# Pure_Sequencer.net
KiCad netlist of a schematic drawn in EAGLE
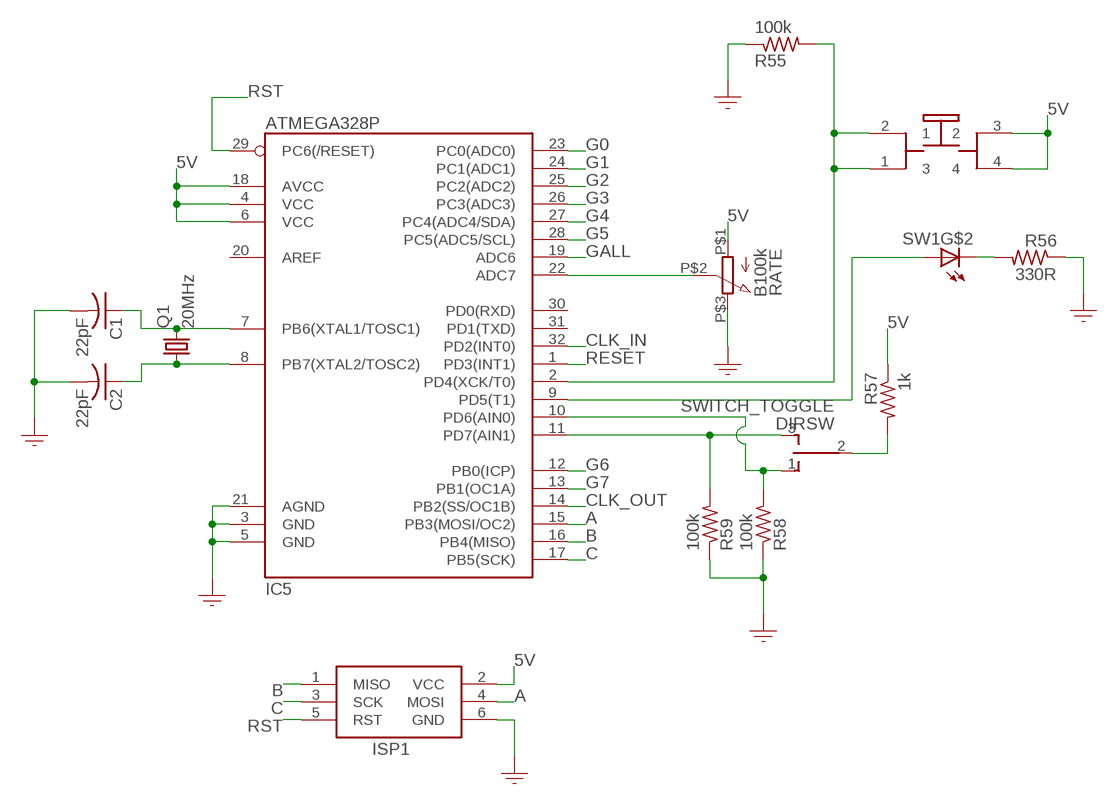
[diagram p0: schematic, sheet 1]
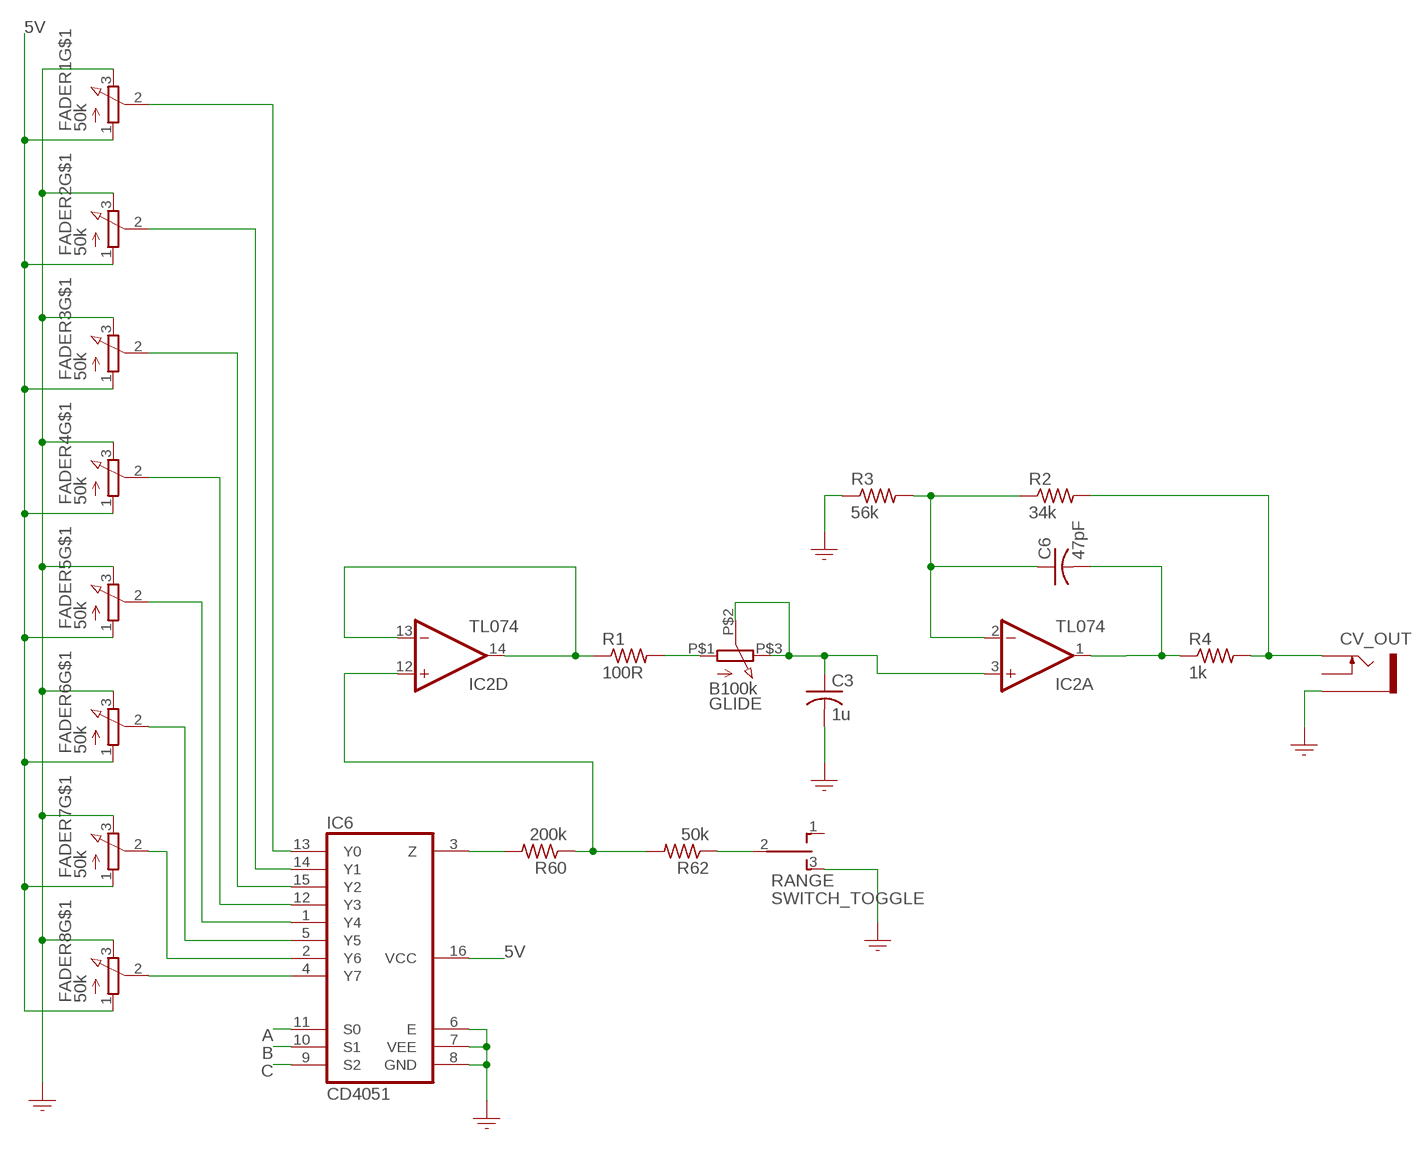
[diagram p1: schematic, sheet 2]
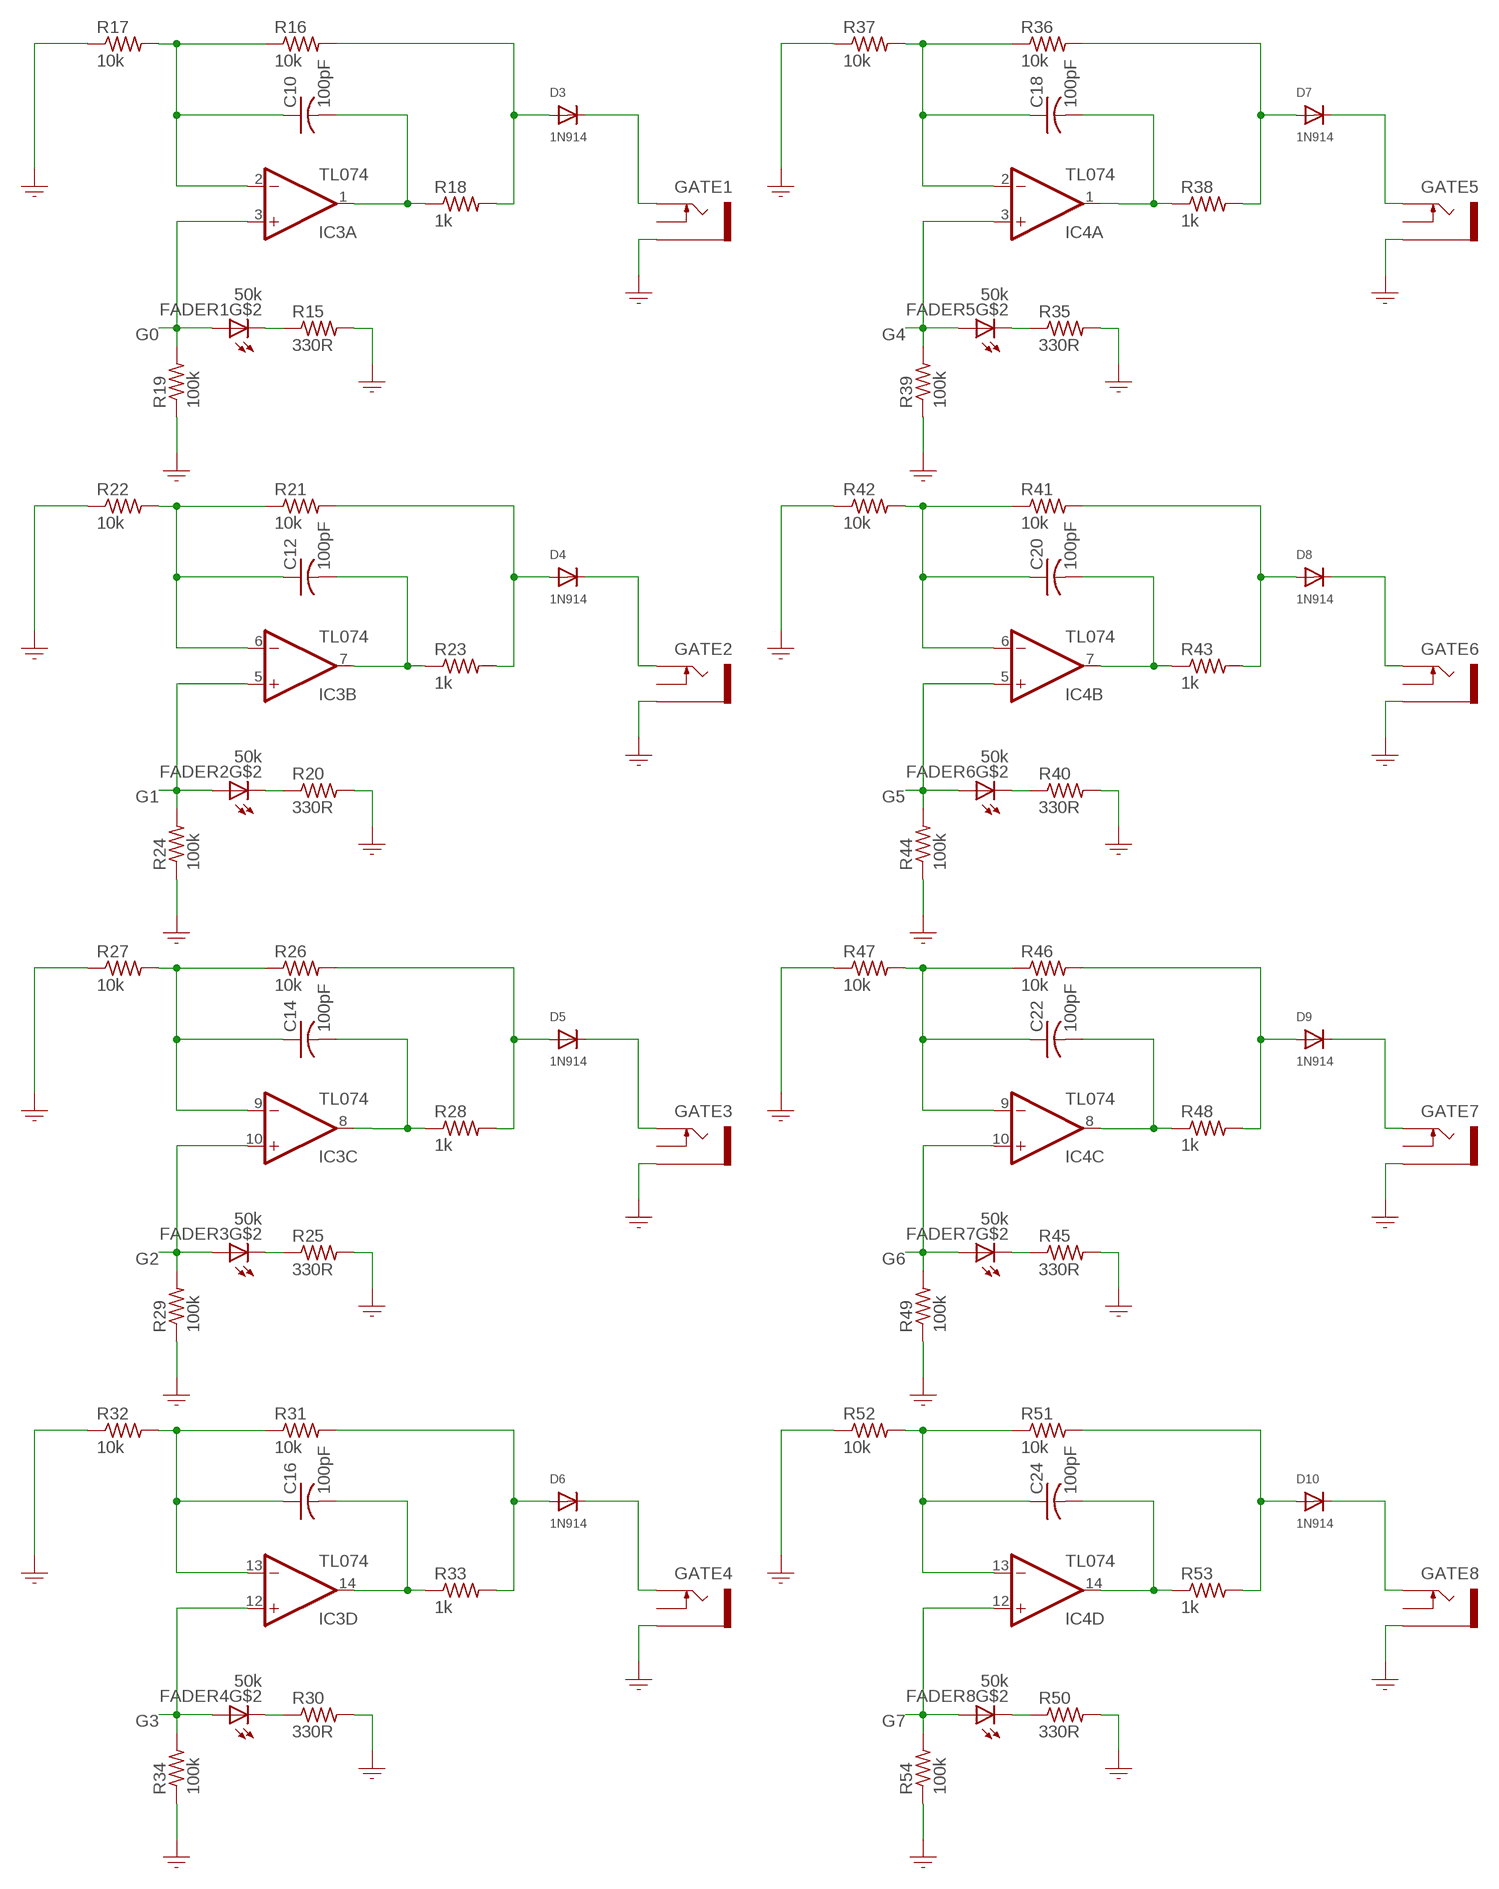
[diagram p2: schematic, sheet 3]
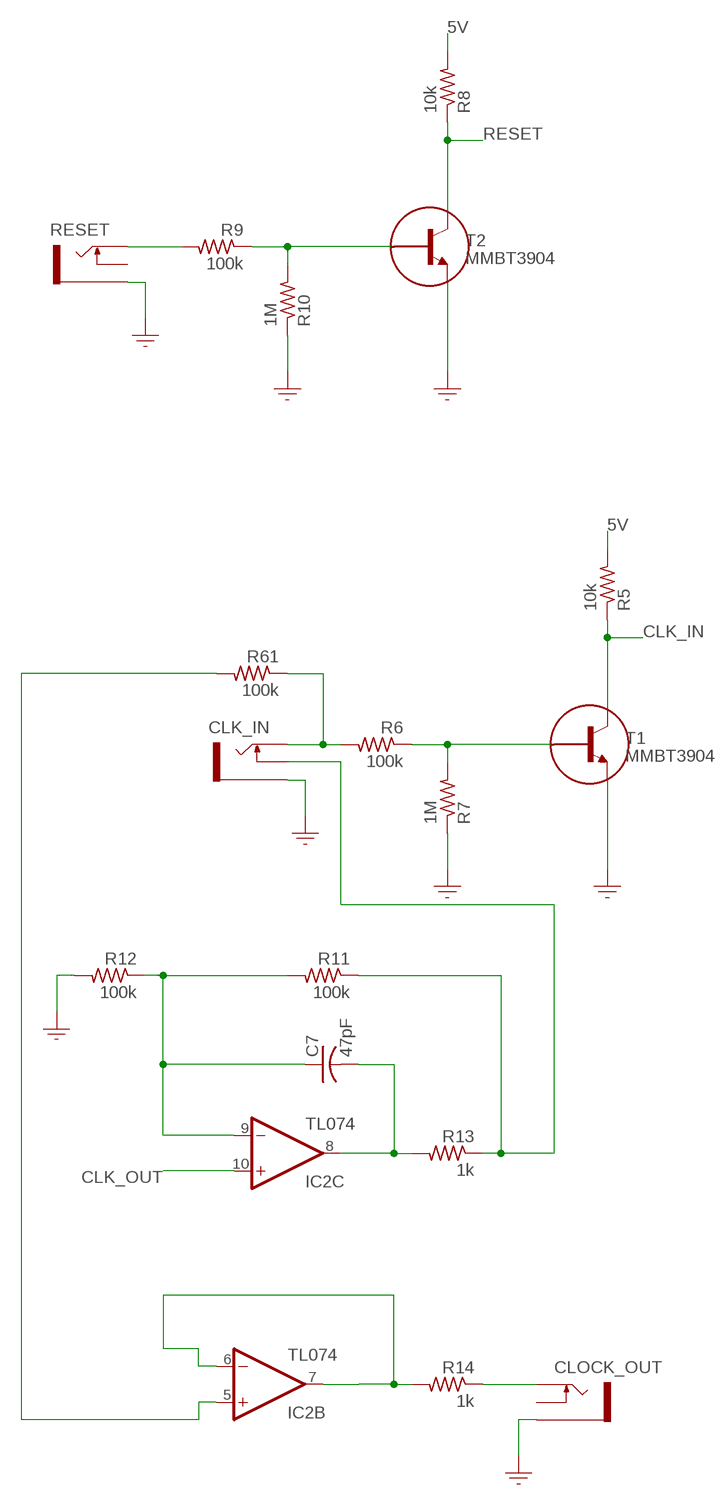
[diagram p3: schematic, sheet 4]
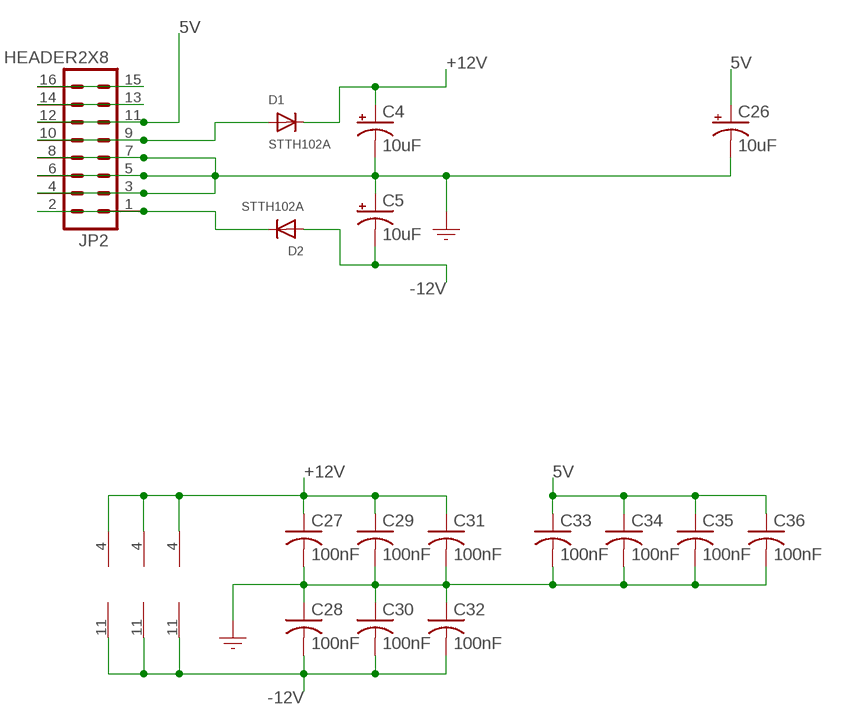
[diagram p4: schematic, sheet 5]

(export (version "E")
  (design (tool "Eeschema 10.0.6"))
  (components
    (comp (ref "C7")
      (value "47pF")
      (footprint "eagle-import:C0805")
      (libsource (lib "eagle-import") (part "CAPACITOR-USC0805"))
    )
    (comp (ref "CLK_IN")
      (value "PJ301M-12")
      (footprint "eagle-import:PJ301M-12")
      (libsource (lib "eagle-import") (part "SOCKET_MONO_3.5MMPJ301M-12"))
    )
    (comp (ref "CLOCK_OUT")
      (value "PJ301M-12")
      (footprint "eagle-import:PJ301M-12")
      (libsource (lib "eagle-import") (part "SOCKET_MONO_3.5MMPJ301M-12"))
    )
    (comp (ref "IC2")
      (value "TL074")
      (footprint "eagle-import:SO14")
      (libsource (lib "eagle-import") (part "OPAMP_QUADD"))
    )
    (comp (ref "R5")
      (value "10k")
      (footprint "eagle-import:R0805")
      (libsource (lib "eagle-import") (part "RESISTOR_USR0805"))
    )
    (comp (ref "R6")
      (value "100k")
      (footprint "eagle-import:R0805")
      (libsource (lib "eagle-import") (part "RESISTOR_USR0805"))
    )
    (comp (ref "R7")
      (value "1M")
      (footprint "eagle-import:R0805")
      (libsource (lib "eagle-import") (part "RESISTOR_USR0805"))
    )
    (comp (ref "R8")
      (value "10k")
      (footprint "eagle-import:R0805")
      (libsource (lib "eagle-import") (part "RESISTOR_USR0805"))
    )
    (comp (ref "R9")
      (value "100k")
      (footprint "eagle-import:R0805")
      (libsource (lib "eagle-import") (part "RESISTOR_USR0805"))
    )
    (comp (ref "R10")
      (value "1M")
      (footprint "eagle-import:R0805")
      (libsource (lib "eagle-import") (part "RESISTOR_USR0805"))
    )
    (comp (ref "R11")
      (value "100k")
      (footprint "eagle-import:R0805")
      (libsource (lib "eagle-import") (part "RESISTOR_USR0805"))
    )
    (comp (ref "R12")
      (value "100k")
      (footprint "eagle-import:R0805")
      (libsource (lib "eagle-import") (part "RESISTOR_USR0805"))
    )
    (comp (ref "R13")
      (value "1k")
      (footprint "eagle-import:R0805")
      (libsource (lib "eagle-import") (part "RESISTOR_USR0805"))
    )
    (comp (ref "R14")
      (value "1k")
      (footprint "eagle-import:R0805")
      (libsource (lib "eagle-import") (part "RESISTOR_USR0805"))
    )
    (comp (ref "R61")
      (value "100k")
      (footprint "eagle-import:R0805")
      (libsource (lib "eagle-import") (part "RESISTOR_USR0805"))
    )
    (comp (ref "RESET")
      (value "PJ301M-12")
      (footprint "eagle-import:PJ301M-12")
      (libsource (lib "eagle-import") (part "SOCKET_MONO_3.5MMPJ301M-12"))
    )
    (comp (ref "T1")
      (value "MMBT3904")
      (footprint "eagle-import:SOT23")
      (libsource (lib "eagle-import") (part "TRANSISTOR_NPNSOT23"))
    )
    (comp (ref "T2")
      (value "MMBT3904")
      (footprint "eagle-import:SOT23")
      (libsource (lib "eagle-import") (part "TRANSISTOR_NPNSOT23"))
    )
    (comp (ref "C3")
      (value "1u")
      (footprint "eagle-import:C0805")
      (libsource (lib "eagle-import") (part "CAPACITOR-USC0805"))
    )
    (comp (ref "C6")
      (value "47pF")
      (footprint "eagle-import:C0805")
      (libsource (lib "eagle-import") (part "CAPACITOR-USC0805"))
    )
    (comp (ref "CV_OUT")
      (value "PJ301M-12")
      (footprint "eagle-import:PJ301M-12")
      (libsource (lib "eagle-import") (part "SOCKET_MONO_3.5MMPJ301M-12"))
    )
    (comp (ref "FADER1")
      (value "50k")
      (footprint "eagle-import:FADER_20MM_LED")
      (libsource (lib "eagle-import") (part "RESISTOR_VARIABLE_LED"))
    )
    (comp (ref "FADER2")
      (value "50k")
      (footprint "eagle-import:FADER_20MM_LED")
      (libsource (lib "eagle-import") (part "RESISTOR_VARIABLE_LED"))
    )
    (comp (ref "FADER3")
      (value "50k")
      (footprint "eagle-import:FADER_20MM_LED")
      (libsource (lib "eagle-import") (part "RESISTOR_VARIABLE_LED"))
    )
    (comp (ref "FADER4")
      (value "50k")
      (footprint "eagle-import:FADER_20MM_LED")
      (libsource (lib "eagle-import") (part "RESISTOR_VARIABLE_LED"))
    )
    (comp (ref "FADER5")
      (value "50k")
      (footprint "eagle-import:FADER_20MM_LED")
      (libsource (lib "eagle-import") (part "RESISTOR_VARIABLE_LED"))
    )
    (comp (ref "FADER6")
      (value "50k")
      (footprint "eagle-import:FADER_20MM_LED")
      (libsource (lib "eagle-import") (part "RESISTOR_VARIABLE_LED"))
    )
    (comp (ref "FADER7")
      (value "50k")
      (footprint "eagle-import:FADER_20MM_LED")
      (libsource (lib "eagle-import") (part "RESISTOR_VARIABLE_LED"))
    )
    (comp (ref "FADER8")
      (value "50k")
      (footprint "eagle-import:FADER_20MM_LED")
      (libsource (lib "eagle-import") (part "RESISTOR_VARIABLE_LED"))
    )
    (comp (ref "GLIDE")
      (value "B100k")
      (footprint "eagle-import:POTENTIOMETER_9MM")
      (libsource (lib "eagle-import") (part "RESISTOR_VARIABLE9MM_POT"))
    )
    (comp (ref "IC6")
      (value "CD4051")
      (footprint "eagle-import:SOIC_16")
      (libsource (lib "eagle-import") (part "MUX_1X8_CD4051"))
    )
    (comp (ref "R1")
      (value "100R")
      (footprint "eagle-import:R0805")
      (libsource (lib "eagle-import") (part "RESISTOR_USR0805"))
    )
    (comp (ref "R2")
      (value "34k")
      (footprint "eagle-import:R0805")
      (libsource (lib "eagle-import") (part "RESISTOR_USR0805"))
    )
    (comp (ref "R3")
      (value "56k")
      (footprint "eagle-import:R0805")
      (libsource (lib "eagle-import") (part "RESISTOR_USR0805"))
    )
    (comp (ref "R4")
      (value "1k")
      (footprint "eagle-import:R0805")
      (libsource (lib "eagle-import") (part "RESISTOR_USR0805"))
    )
    (comp (ref "R60")
      (value "200k")
      (footprint "eagle-import:R0805")
      (libsource (lib "eagle-import") (part "RESISTOR_USR0805"))
    )
    (comp (ref "R62")
      (value "50k")
      (footprint "eagle-import:R0805")
      (libsource (lib "eagle-import") (part "RESISTOR_USR0805"))
    )
    (comp (ref "RANGE")
      (value "SWITCH_TOGGLE")
      (footprint "eagle-import:TOGGLE_SW")
      (libsource (lib "eagle-import") (part "SWITCH_TOGGLE"))
    )
    (comp (ref "C10")
      (value "100pF")
      (footprint "eagle-import:C0805")
      (libsource (lib "eagle-import") (part "CAPACITOR-USC0805"))
    )
    (comp (ref "C12")
      (value "100pF")
      (footprint "eagle-import:C0805")
      (libsource (lib "eagle-import") (part "CAPACITOR-USC0805"))
    )
    (comp (ref "C14")
      (value "100pF")
      (footprint "eagle-import:C0805")
      (libsource (lib "eagle-import") (part "CAPACITOR-USC0805"))
    )
    (comp (ref "C16")
      (value "100pF")
      (footprint "eagle-import:C0805")
      (libsource (lib "eagle-import") (part "CAPACITOR-USC0805"))
    )
    (comp (ref "C18")
      (value "100pF")
      (footprint "eagle-import:C0805")
      (libsource (lib "eagle-import") (part "CAPACITOR-USC0805"))
    )
    (comp (ref "C20")
      (value "100pF")
      (footprint "eagle-import:C0805")
      (libsource (lib "eagle-import") (part "CAPACITOR-USC0805"))
    )
    (comp (ref "C22")
      (value "100pF")
      (footprint "eagle-import:C0805")
      (libsource (lib "eagle-import") (part "CAPACITOR-USC0805"))
    )
    (comp (ref "C24")
      (value "100pF")
      (footprint "eagle-import:C0805")
      (libsource (lib "eagle-import") (part "CAPACITOR-USC0805"))
    )
    (comp (ref "D3")
      (value "1N914")
      (footprint "eagle-import:DO-41")
      (libsource (lib "eagle-import") (part "DIODEDO-41"))
    )
    (comp (ref "D4")
      (value "1N914")
      (footprint "eagle-import:DO-41")
      (libsource (lib "eagle-import") (part "DIODEDO-41"))
    )
    (comp (ref "D5")
      (value "1N914")
      (footprint "eagle-import:DO-41")
      (libsource (lib "eagle-import") (part "DIODEDO-41"))
    )
    (comp (ref "D6")
      (value "1N914")
      (footprint "eagle-import:DO-41")
      (libsource (lib "eagle-import") (part "DIODEDO-41"))
    )
    (comp (ref "D7")
      (value "1N914")
      (footprint "eagle-import:DO-41")
      (libsource (lib "eagle-import") (part "DIODEDO-41"))
    )
    (comp (ref "D8")
      (value "1N914")
      (footprint "eagle-import:DO-41")
      (libsource (lib "eagle-import") (part "DIODEDO-41"))
    )
    (comp (ref "D9")
      (value "1N914")
      (footprint "eagle-import:DO-41")
      (libsource (lib "eagle-import") (part "DIODEDO-41"))
    )
    (comp (ref "D10")
      (value "1N914")
      (footprint "eagle-import:DO-41")
      (libsource (lib "eagle-import") (part "DIODEDO-41"))
    )
    (comp (ref "GATE1")
      (value "PJ301M-12")
      (footprint "eagle-import:PJ301M-12")
      (libsource (lib "eagle-import") (part "SOCKET_MONO_3.5MMPJ301M-12"))
    )
    (comp (ref "GATE2")
      (value "PJ301M-12")
      (footprint "eagle-import:PJ301M-12")
      (libsource (lib "eagle-import") (part "SOCKET_MONO_3.5MMPJ301M-12"))
    )
    (comp (ref "GATE3")
      (value "PJ301M-12")
      (footprint "eagle-import:PJ301M-12")
      (libsource (lib "eagle-import") (part "SOCKET_MONO_3.5MMPJ301M-12"))
    )
    (comp (ref "GATE4")
      (value "PJ301M-12")
      (footprint "eagle-import:PJ301M-12")
      (libsource (lib "eagle-import") (part "SOCKET_MONO_3.5MMPJ301M-12"))
    )
    (comp (ref "GATE5")
      (value "PJ301M-12")
      (footprint "eagle-import:PJ301M-12")
      (libsource (lib "eagle-import") (part "SOCKET_MONO_3.5MMPJ301M-12"))
    )
    (comp (ref "GATE6")
      (value "PJ301M-12")
      (footprint "eagle-import:PJ301M-12")
      (libsource (lib "eagle-import") (part "SOCKET_MONO_3.5MMPJ301M-12"))
    )
    (comp (ref "GATE7")
      (value "PJ301M-12")
      (footprint "eagle-import:PJ301M-12")
      (libsource (lib "eagle-import") (part "SOCKET_MONO_3.5MMPJ301M-12"))
    )
    (comp (ref "GATE8")
      (value "PJ301M-12")
      (footprint "eagle-import:PJ301M-12")
      (libsource (lib "eagle-import") (part "SOCKET_MONO_3.5MMPJ301M-12"))
    )
    (comp (ref "IC3")
      (value "TL074")
      (footprint "eagle-import:SO14")
      (libsource (lib "eagle-import") (part "OPAMP_QUADD"))
    )
    (comp (ref "IC4")
      (value "TL074")
      (footprint "eagle-import:SO14")
      (libsource (lib "eagle-import") (part "OPAMP_QUADD"))
    )
    (comp (ref "R15")
      (value "330R")
      (footprint "eagle-import:R0805")
      (libsource (lib "eagle-import") (part "RESISTOR_USR0805"))
    )
    (comp (ref "R16")
      (value "10k")
      (footprint "eagle-import:R0805")
      (libsource (lib "eagle-import") (part "RESISTOR_USR0805"))
    )
    (comp (ref "R17")
      (value "10k")
      (footprint "eagle-import:R0805")
      (libsource (lib "eagle-import") (part "RESISTOR_USR0805"))
    )
    (comp (ref "R18")
      (value "1k")
      (footprint "eagle-import:R0805")
      (libsource (lib "eagle-import") (part "RESISTOR_USR0805"))
    )
    (comp (ref "R19")
      (value "100k")
      (footprint "eagle-import:R0805")
      (libsource (lib "eagle-import") (part "RESISTOR_USR0805"))
    )
    (comp (ref "R20")
      (value "330R")
      (footprint "eagle-import:R0805")
      (libsource (lib "eagle-import") (part "RESISTOR_USR0805"))
    )
    (comp (ref "R21")
      (value "10k")
      (footprint "eagle-import:R0805")
      (libsource (lib "eagle-import") (part "RESISTOR_USR0805"))
    )
    (comp (ref "R22")
      (value "10k")
      (footprint "eagle-import:R0805")
      (libsource (lib "eagle-import") (part "RESISTOR_USR0805"))
    )
    (comp (ref "R23")
      (value "1k")
      (footprint "eagle-import:R0805")
      (libsource (lib "eagle-import") (part "RESISTOR_USR0805"))
    )
    (comp (ref "R24")
      (value "100k")
      (footprint "eagle-import:R0805")
      (libsource (lib "eagle-import") (part "RESISTOR_USR0805"))
    )
    (comp (ref "R25")
      (value "330R")
      (footprint "eagle-import:R0805")
      (libsource (lib "eagle-import") (part "RESISTOR_USR0805"))
    )
    (comp (ref "R26")
      (value "10k")
      (footprint "eagle-import:R0805")
      (libsource (lib "eagle-import") (part "RESISTOR_USR0805"))
    )
    (comp (ref "R27")
      (value "10k")
      (footprint "eagle-import:R0805")
      (libsource (lib "eagle-import") (part "RESISTOR_USR0805"))
    )
    (comp (ref "R28")
      (value "1k")
      (footprint "eagle-import:R0805")
      (libsource (lib "eagle-import") (part "RESISTOR_USR0805"))
    )
    (comp (ref "R29")
      (value "100k")
      (footprint "eagle-import:R0805")
      (libsource (lib "eagle-import") (part "RESISTOR_USR0805"))
    )
    (comp (ref "R30")
      (value "330R")
      (footprint "eagle-import:R0805")
      (libsource (lib "eagle-import") (part "RESISTOR_USR0805"))
    )
    (comp (ref "R31")
      (value "10k")
      (footprint "eagle-import:R0805")
      (libsource (lib "eagle-import") (part "RESISTOR_USR0805"))
    )
    (comp (ref "R32")
      (value "10k")
      (footprint "eagle-import:R0805")
      (libsource (lib "eagle-import") (part "RESISTOR_USR0805"))
    )
    (comp (ref "R33")
      (value "1k")
      (footprint "eagle-import:R0805")
      (libsource (lib "eagle-import") (part "RESISTOR_USR0805"))
    )
    (comp (ref "R34")
      (value "100k")
      (footprint "eagle-import:R0805")
      (libsource (lib "eagle-import") (part "RESISTOR_USR0805"))
    )
    (comp (ref "R35")
      (value "330R")
      (footprint "eagle-import:R0805")
      (libsource (lib "eagle-import") (part "RESISTOR_USR0805"))
    )
    (comp (ref "R36")
      (value "10k")
      (footprint "eagle-import:R0805")
      (libsource (lib "eagle-import") (part "RESISTOR_USR0805"))
    )
    (comp (ref "R37")
      (value "10k")
      (footprint "eagle-import:R0805")
      (libsource (lib "eagle-import") (part "RESISTOR_USR0805"))
    )
    (comp (ref "R38")
      (value "1k")
      (footprint "eagle-import:R0805")
      (libsource (lib "eagle-import") (part "RESISTOR_USR0805"))
    )
    (comp (ref "R39")
      (value "100k")
      (footprint "eagle-import:R0805")
      (libsource (lib "eagle-import") (part "RESISTOR_USR0805"))
    )
    (comp (ref "R40")
      (value "330R")
      (footprint "eagle-import:R0805")
      (libsource (lib "eagle-import") (part "RESISTOR_USR0805"))
    )
    (comp (ref "R41")
      (value "10k")
      (footprint "eagle-import:R0805")
      (libsource (lib "eagle-import") (part "RESISTOR_USR0805"))
    )
    (comp (ref "R42")
      (value "10k")
      (footprint "eagle-import:R0805")
      (libsource (lib "eagle-import") (part "RESISTOR_USR0805"))
    )
    (comp (ref "R43")
      (value "1k")
      (footprint "eagle-import:R0805")
      (libsource (lib "eagle-import") (part "RESISTOR_USR0805"))
    )
    (comp (ref "R44")
      (value "100k")
      (footprint "eagle-import:R0805")
      (libsource (lib "eagle-import") (part "RESISTOR_USR0805"))
    )
    (comp (ref "R45")
      (value "330R")
      (footprint "eagle-import:R0805")
      (libsource (lib "eagle-import") (part "RESISTOR_USR0805"))
    )
    (comp (ref "R46")
      (value "10k")
      (footprint "eagle-import:R0805")
      (libsource (lib "eagle-import") (part "RESISTOR_USR0805"))
    )
    (comp (ref "R47")
      (value "10k")
      (footprint "eagle-import:R0805")
      (libsource (lib "eagle-import") (part "RESISTOR_USR0805"))
    )
    (comp (ref "R48")
      (value "1k")
      (footprint "eagle-import:R0805")
      (libsource (lib "eagle-import") (part "RESISTOR_USR0805"))
    )
    (comp (ref "R49")
      (value "100k")
      (footprint "eagle-import:R0805")
      (libsource (lib "eagle-import") (part "RESISTOR_USR0805"))
    )
    (comp (ref "R50")
      (value "330R")
      (footprint "eagle-import:R0805")
      (libsource (lib "eagle-import") (part "RESISTOR_USR0805"))
    )
    (comp (ref "R51")
      (value "10k")
      (footprint "eagle-import:R0805")
      (libsource (lib "eagle-import") (part "RESISTOR_USR0805"))
    )
    (comp (ref "R52")
      (value "10k")
      (footprint "eagle-import:R0805")
      (libsource (lib "eagle-import") (part "RESISTOR_USR0805"))
    )
    (comp (ref "R53")
      (value "1k")
      (footprint "eagle-import:R0805")
      (libsource (lib "eagle-import") (part "RESISTOR_USR0805"))
    )
    (comp (ref "R54")
      (value "100k")
      (footprint "eagle-import:R0805")
      (libsource (lib "eagle-import") (part "RESISTOR_USR0805"))
    )
    (comp (ref "C1")
      (value "22pF")
      (footprint "eagle-import:C0805")
      (libsource (lib "eagle-import") (part "CAPACITOR-USC0805"))
    )
    (comp (ref "C2")
      (value "22pF")
      (footprint "eagle-import:C0805")
      (libsource (lib "eagle-import") (part "CAPACITOR-USC0805"))
    )
    (comp (ref "DIRSW")
      (value "SWITCH_TOGGLE")
      (footprint "eagle-import:TOGGLE_SW")
      (libsource (lib "eagle-import") (part "SWITCH_TOGGLE"))
    )
    (comp (ref "IC5")
      (value "ATMEGA328P")
      (footprint "eagle-import:TQFP32-08")
      (libsource (lib "eagle-import") (part "MICROPROCESSOR_ATMEGA328_SMT"))
    )
    (comp (ref "ISP1")
      (value "HEADER2X3-6")
      (footprint "eagle-import:AVRISP")
      (libsource (lib "eagle-import") (part "HEADER2X3-6"))
    )
    (comp (ref "Q1")
      (value "20MHz")
      (footprint "eagle-import:HC49UP")
      (libsource (lib "eagle-import") (part "CRYSTALHC49UP"))
    )
    (comp (ref "R55")
      (value "100k")
      (footprint "eagle-import:R0805")
      (libsource (lib "eagle-import") (part "RESISTOR_USR0805"))
    )
    (comp (ref "R56")
      (value "330R")
      (footprint "eagle-import:R0805")
      (libsource (lib "eagle-import") (part "RESISTOR_USR0805"))
    )
    (comp (ref "R57")
      (value "1k")
      (footprint "eagle-import:R0805")
      (libsource (lib "eagle-import") (part "RESISTOR_USR0805"))
    )
    (comp (ref "R58")
      (value "100k")
      (footprint "eagle-import:R0805")
      (libsource (lib "eagle-import") (part "RESISTOR_USR0805"))
    )
    (comp (ref "R59")
      (value "100k")
      (footprint "eagle-import:R0805")
      (libsource (lib "eagle-import") (part "RESISTOR_USR0805"))
    )
    (comp (ref "RATE")
      (value "B100k")
      (footprint "eagle-import:POTENTIOMETER_9MM")
      (libsource (lib "eagle-import") (part "RESISTOR_VARIABLE9MM_POT"))
    )
    (comp (ref "SW1")
      (value "SWITCH_PUSHBUTTON_LED")
      (footprint "eagle-import:PB6149L")
      (libsource (lib "eagle-import") (part "SWITCH_PUSHBUTTON_LED"))
    )
    (comp (ref "C4")
      (value "10uF")
      (footprint "eagle-import:153CLV-0505")
      (libsource (lib "eagle-import") (part "CAPACITOR_POL-US153CLV-0505"))
    )
    (comp (ref "C5")
      (value "10uF")
      (footprint "eagle-import:153CLV-0505")
      (libsource (lib "eagle-import") (part "CAPACITOR_POL-US153CLV-0505"))
    )
    (comp (ref "C26")
      (value "10uF")
      (footprint "eagle-import:153CLV-0505")
      (libsource (lib "eagle-import") (part "CAPACITOR_POL-US153CLV-0505"))
    )
    (comp (ref "C27")
      (value "100nF")
      (footprint "eagle-import:C0805")
      (libsource (lib "eagle-import") (part "CAPACITOR-USC0805"))
    )
    (comp (ref "C28")
      (value "100nF")
      (footprint "eagle-import:C0805")
      (libsource (lib "eagle-import") (part "CAPACITOR-USC0805"))
    )
    (comp (ref "C29")
      (value "100nF")
      (footprint "eagle-import:C0805")
      (libsource (lib "eagle-import") (part "CAPACITOR-USC0805"))
    )
    (comp (ref "C30")
      (value "100nF")
      (footprint "eagle-import:C0805")
      (libsource (lib "eagle-import") (part "CAPACITOR-USC0805"))
    )
    (comp (ref "C31")
      (value "100nF")
      (footprint "eagle-import:C0805")
      (libsource (lib "eagle-import") (part "CAPACITOR-USC0805"))
    )
    (comp (ref "C32")
      (value "100nF")
      (footprint "eagle-import:C0805")
      (libsource (lib "eagle-import") (part "CAPACITOR-USC0805"))
    )
    (comp (ref "C33")
      (value "100nF")
      (footprint "eagle-import:C0805")
      (libsource (lib "eagle-import") (part "CAPACITOR-USC0805"))
    )
    (comp (ref "C34")
      (value "100nF")
      (footprint "eagle-import:C0805")
      (libsource (lib "eagle-import") (part "CAPACITOR-USC0805"))
    )
    (comp (ref "C35")
      (value "100nF")
      (footprint "eagle-import:C0805")
      (libsource (lib "eagle-import") (part "CAPACITOR-USC0805"))
    )
    (comp (ref "C36")
      (value "100nF")
      (footprint "eagle-import:C0805")
      (libsource (lib "eagle-import") (part "CAPACITOR-USC0805"))
    )
    (comp (ref "D1")
      (value "STTH102A")
      (footprint "eagle-import:SMADIODE")
      (libsource (lib "eagle-import") (part "DIODESMA"))
    )
    (comp (ref "D2")
      (value "STTH102A")
      (footprint "eagle-import:SMADIODE")
      (libsource (lib "eagle-import") (part "DIODESMA"))
    )
    (comp (ref "JP2")
      (value "HEADER2X8")
      (footprint "eagle-import:POWER_SHROUDED")
      (libsource (lib "eagle-import") (part "HEADER2X8"))
    )
  )
  (nets
    (net (code "1") (name "+12V") (class "Default")
      (node (ref "C27") (pin "1") (pinfunction "1_1") (pintype "passive"))
      (node (ref "C29") (pin "1") (pinfunction "1_1") (pintype "passive"))
      (node (ref "C31") (pin "1") (pinfunction "1_1") (pintype "passive"))
      (node (ref "C4") (pin "+") (pinfunction "+_+") (pintype "passive"))
      (node (ref "D1") (pin "C") (pinfunction "C_C") (pintype "passive"))
      (node (ref "IC2") (pin "4") (pinfunction "V+_4") (pintype "power_in"))
      (node (ref "IC3") (pin "4") (pinfunction "V+_4") (pintype "power_in"))
      (node (ref "IC4") (pin "4") (pinfunction "V+_4") (pintype "power_in"))
    )
    (net (code "2") (name "-12V") (class "Default")
      (node (ref "C28") (pin "2") (pinfunction "2_2") (pintype "passive"))
      (node (ref "C30") (pin "2") (pinfunction "2_2") (pintype "passive"))
      (node (ref "C32") (pin "2") (pinfunction "2_2") (pintype "passive"))
      (node (ref "C5") (pin "-") (pinfunction "-_-") (pintype "passive"))
      (node (ref "D2") (pin "A") (pinfunction "A_A") (pintype "passive"))
      (node (ref "IC2") (pin "11") (pinfunction "V-_11") (pintype "power_in"))
      (node (ref "IC3") (pin "11") (pinfunction "V-_11") (pintype "power_in"))
      (node (ref "IC4") (pin "11") (pinfunction "V-_11") (pintype "power_in"))
    )
    (net (code "3") (name "5V") (class "Default")
      (node (ref "C26") (pin "+") (pinfunction "+_+") (pintype "passive"))
      (node (ref "C33") (pin "1") (pinfunction "1_1") (pintype "passive"))
      (node (ref "C34") (pin "1") (pinfunction "1_1") (pintype "passive"))
      (node (ref "C35") (pin "1") (pinfunction "1_1") (pintype "passive"))
      (node (ref "C36") (pin "1") (pinfunction "1_1") (pintype "passive"))
      (node (ref "FADER1") (pin "1") (pinfunction "1_1") (pintype "passive"))
      (node (ref "FADER2") (pin "1") (pinfunction "1_1") (pintype "passive"))
      (node (ref "FADER3") (pin "1") (pinfunction "1_1") (pintype "passive"))
      (node (ref "FADER4") (pin "1") (pinfunction "1_1") (pintype "passive"))
      (node (ref "FADER5") (pin "1") (pinfunction "1_1") (pintype "passive"))
      (node (ref "FADER6") (pin "1") (pinfunction "1_1") (pintype "passive"))
      (node (ref "FADER7") (pin "1") (pinfunction "1_1") (pintype "passive"))
      (node (ref "FADER8") (pin "1") (pinfunction "1_1") (pintype "passive"))
      (node (ref "IC5") (pin "18") (pinfunction "AVCC_18") (pintype "bidirectional"))
      (node (ref "IC5") (pin "4") (pinfunction "VCC_4") (pintype "bidirectional"))
      (node (ref "IC5") (pin "6") (pinfunction "VCC_6") (pintype "bidirectional"))
      (node (ref "IC6") (pin "16") (pinfunction "VCC_16") (pintype "input"))
      (node (ref "ISP1") (pin "2") (pinfunction "VCC_2") (pintype "power_in"))
      (node (ref "JP2") (pin "11") (pinfunction "11_11") (pintype "passive"))
      (node (ref "JP2") (pin "12") (pinfunction "12_12") (pintype "passive"))
      (node (ref "R5") (pin "2") (pinfunction "2_2") (pintype "passive"))
      (node (ref "R57") (pin "1") (pinfunction "1_1") (pintype "passive"))
      (node (ref "R8") (pin "2") (pinfunction "2_2") (pintype "passive"))
      (node (ref "RATE") (pin "P$1") (pinfunction "1_P$1") (pintype "passive"))
      (node (ref "SW1") (pin "3") (pinfunction "2_3") (pintype "bidirectional"))
      (node (ref "SW1") (pin "4") (pinfunction "4_4") (pintype "bidirectional"))
    )
    (net (code "4") (name "A") (class "Default")
      (node (ref "IC5") (pin "15") (pinfunction "PB3(MOSI/OC2)_15") (pintype "bidirectional"))
      (node (ref "IC6") (pin "11") (pinfunction "S0_11") (pintype "input"))
      (node (ref "ISP1") (pin "4") (pinfunction "MOSI_4") (pintype "output"))
    )
    (net (code "5") (name "B") (class "Default")
      (node (ref "IC5") (pin "16") (pinfunction "PB4(MISO)_16") (pintype "bidirectional"))
      (node (ref "IC6") (pin "10") (pinfunction "S1_10") (pintype "input"))
      (node (ref "ISP1") (pin "1") (pinfunction "MISO_1") (pintype "input"))
    )
    (net (code "6") (name "C") (class "Default")
      (node (ref "IC5") (pin "17") (pinfunction "PB5(SCK)_17") (pintype "bidirectional"))
      (node (ref "IC6") (pin "9") (pinfunction "S2_9") (pintype "input"))
      (node (ref "ISP1") (pin "3") (pinfunction "SCK_3") (pintype "output"))
    )
    (net (code "7") (name "CLK_IN") (class "Default")
      (node (ref "IC5") (pin "32") (pinfunction "PD2(INT0)_32") (pintype "bidirectional"))
      (node (ref "R5") (pin "1") (pinfunction "1_1") (pintype "passive"))
      (node (ref "T1") (pin "3") (pinfunction "C_3") (pintype "passive"))
    )
    (net (code "8") (name "CLK_OUT") (class "Default")
      (node (ref "IC2") (pin "10") (pinfunction "+IN_10") (pintype "input"))
      (node (ref "IC5") (pin "14") (pinfunction "PB2(SS/OC1B)_14") (pintype "bidirectional"))
    )
    (net (code "9") (name "G0") (class "Default")
      (node (ref "FADER1") (pin "A") (pinfunction "A_A") (pintype "passive"))
      (node (ref "IC3") (pin "3") (pinfunction "+IN_3") (pintype "input"))
      (node (ref "IC5") (pin "23") (pinfunction "PC0(ADC0)_23") (pintype "bidirectional"))
      (node (ref "R19") (pin "2") (pinfunction "2_2") (pintype "passive"))
    )
    (net (code "10") (name "G1") (class "Default")
      (node (ref "FADER2") (pin "A") (pinfunction "A_A") (pintype "passive"))
      (node (ref "IC3") (pin "5") (pinfunction "+IN_5") (pintype "input"))
      (node (ref "IC5") (pin "24") (pinfunction "PC1(ADC1)_24") (pintype "bidirectional"))
      (node (ref "R24") (pin "2") (pinfunction "2_2") (pintype "passive"))
    )
    (net (code "11") (name "G2") (class "Default")
      (node (ref "FADER3") (pin "A") (pinfunction "A_A") (pintype "passive"))
      (node (ref "IC3") (pin "10") (pinfunction "+IN_10") (pintype "input"))
      (node (ref "IC5") (pin "25") (pinfunction "PC2(ADC2)_25") (pintype "bidirectional"))
      (node (ref "R29") (pin "2") (pinfunction "2_2") (pintype "passive"))
    )
    (net (code "12") (name "G3") (class "Default")
      (node (ref "FADER4") (pin "A") (pinfunction "A_A") (pintype "passive"))
      (node (ref "IC3") (pin "12") (pinfunction "+IN_12") (pintype "input"))
      (node (ref "IC5") (pin "26") (pinfunction "PC3(ADC3)_26") (pintype "bidirectional"))
      (node (ref "R34") (pin "2") (pinfunction "2_2") (pintype "passive"))
    )
    (net (code "13") (name "G4") (class "Default")
      (node (ref "FADER5") (pin "A") (pinfunction "A_A") (pintype "passive"))
      (node (ref "IC4") (pin "3") (pinfunction "+IN_3") (pintype "input"))
      (node (ref "IC5") (pin "27") (pinfunction "PC4(ADC4/SDA)_27") (pintype "bidirectional"))
      (node (ref "R39") (pin "2") (pinfunction "2_2") (pintype "passive"))
    )
    (net (code "14") (name "G5") (class "Default")
      (node (ref "FADER6") (pin "A") (pinfunction "A_A") (pintype "passive"))
      (node (ref "IC4") (pin "5") (pinfunction "+IN_5") (pintype "input"))
      (node (ref "IC5") (pin "28") (pinfunction "PC5(ADC5/SCL)_28") (pintype "bidirectional"))
      (node (ref "R44") (pin "2") (pinfunction "2_2") (pintype "passive"))
    )
    (net (code "15") (name "G6") (class "Default")
      (node (ref "FADER7") (pin "A") (pinfunction "A_A") (pintype "passive"))
      (node (ref "IC4") (pin "10") (pinfunction "+IN_10") (pintype "input"))
      (node (ref "IC5") (pin "12") (pinfunction "PB0(ICP)_12") (pintype "bidirectional"))
      (node (ref "R49") (pin "2") (pinfunction "2_2") (pintype "passive"))
    )
    (net (code "16") (name "G7") (class "Default")
      (node (ref "FADER8") (pin "A") (pinfunction "A_A") (pintype "passive"))
      (node (ref "IC4") (pin "12") (pinfunction "+IN_12") (pintype "input"))
      (node (ref "IC5") (pin "13") (pinfunction "PB1(OC1A)_13") (pintype "bidirectional"))
      (node (ref "R54") (pin "2") (pinfunction "2_2") (pintype "passive"))
    )
    (net (code "17") (name "GALL") (class "Default")
      (node (ref "IC5") (pin "19") (pinfunction "ADC6_19") (pintype "bidirectional"))
    )
    (net (code "18") (name "GND") (class "Default")
      (node (ref "C1") (pin "2") (pinfunction "2_2") (pintype "passive"))
      (node (ref "C2") (pin "2") (pinfunction "2_2") (pintype "passive"))
      (node (ref "C26") (pin "-") (pinfunction "-_-") (pintype "passive"))
      (node (ref "C27") (pin "2") (pinfunction "2_2") (pintype "passive"))
      (node (ref "C28") (pin "1") (pinfunction "1_1") (pintype "passive"))
      (node (ref "C29") (pin "2") (pinfunction "2_2") (pintype "passive"))
      (node (ref "C3") (pin "2") (pinfunction "2_2") (pintype "passive"))
      (node (ref "C30") (pin "1") (pinfunction "1_1") (pintype "passive"))
      (node (ref "C31") (pin "2") (pinfunction "2_2") (pintype "passive"))
      (node (ref "C32") (pin "1") (pinfunction "1_1") (pintype "passive"))
      (node (ref "C33") (pin "2") (pinfunction "2_2") (pintype "passive"))
      (node (ref "C34") (pin "2") (pinfunction "2_2") (pintype "passive"))
      (node (ref "C35") (pin "2") (pinfunction "2_2") (pintype "passive"))
      (node (ref "C36") (pin "2") (pinfunction "2_2") (pintype "passive"))
      (node (ref "C4") (pin "-") (pinfunction "-_-") (pintype "passive"))
      (node (ref "C5") (pin "+") (pinfunction "+_+") (pintype "passive"))
      (node (ref "CLK_IN") (pin "GND") (pinfunction "SLEEVE_GND") (pintype "passive"))
      (node (ref "CLOCK_OUT") (pin "GND") (pinfunction "SLEEVE_GND") (pintype "passive"))
      (node (ref "CV_OUT") (pin "GND") (pinfunction "SLEEVE_GND") (pintype "passive"))
      (node (ref "FADER1") (pin "3") (pinfunction "3_3") (pintype "passive"))
      (node (ref "FADER2") (pin "3") (pinfunction "3_3") (pintype "passive"))
      (node (ref "FADER3") (pin "3") (pinfunction "3_3") (pintype "passive"))
      (node (ref "FADER4") (pin "3") (pinfunction "3_3") (pintype "passive"))
      (node (ref "FADER5") (pin "3") (pinfunction "3_3") (pintype "passive"))
      (node (ref "FADER6") (pin "3") (pinfunction "3_3") (pintype "passive"))
      (node (ref "FADER7") (pin "3") (pinfunction "3_3") (pintype "passive"))
      (node (ref "FADER8") (pin "3") (pinfunction "3_3") (pintype "passive"))
      (node (ref "GATE1") (pin "GND") (pinfunction "SLEEVE_GND") (pintype "passive"))
      (node (ref "GATE2") (pin "GND") (pinfunction "SLEEVE_GND") (pintype "passive"))
      (node (ref "GATE3") (pin "GND") (pinfunction "SLEEVE_GND") (pintype "passive"))
      (node (ref "GATE4") (pin "GND") (pinfunction "SLEEVE_GND") (pintype "passive"))
      (node (ref "GATE5") (pin "GND") (pinfunction "SLEEVE_GND") (pintype "passive"))
      (node (ref "GATE6") (pin "GND") (pinfunction "SLEEVE_GND") (pintype "passive"))
      (node (ref "GATE7") (pin "GND") (pinfunction "SLEEVE_GND") (pintype "passive"))
      (node (ref "GATE8") (pin "GND") (pinfunction "SLEEVE_GND") (pintype "passive"))
      (node (ref "IC5") (pin "21") (pinfunction "AGND_21") (pintype "bidirectional"))
      (node (ref "IC5") (pin "3") (pinfunction "GND_3") (pintype "bidirectional"))
      (node (ref "IC5") (pin "5") (pinfunction "GND_5") (pintype "bidirectional"))
      (node (ref "IC6") (pin "6") (pinfunction "E_6") (pintype "bidirectional"))
      (node (ref "IC6") (pin "7") (pinfunction "VEE_7") (pintype "bidirectional"))
      (node (ref "IC6") (pin "8") (pinfunction "GND_8") (pintype "bidirectional"))
      (node (ref "ISP1") (pin "6") (pinfunction "GND_6") (pintype "power_in"))
      (node (ref "JP2") (pin "3") (pinfunction "3_3") (pintype "passive"))
      (node (ref "JP2") (pin "4") (pinfunction "4_4") (pintype "passive"))
      (node (ref "JP2") (pin "5") (pinfunction "5_5") (pintype "passive"))
      (node (ref "JP2") (pin "6") (pinfunction "6_6") (pintype "passive"))
      (node (ref "JP2") (pin "7") (pinfunction "7_7") (pintype "passive"))
      (node (ref "JP2") (pin "8") (pinfunction "8_8") (pintype "passive"))
      (node (ref "R10") (pin "1") (pinfunction "1_1") (pintype "passive"))
      (node (ref "R12") (pin "2") (pinfunction "2_2") (pintype "passive"))
      (node (ref "R15") (pin "2") (pinfunction "2_2") (pintype "passive"))
      (node (ref "R17") (pin "1") (pinfunction "1_1") (pintype "passive"))
      (node (ref "R19") (pin "1") (pinfunction "1_1") (pintype "passive"))
      (node (ref "R20") (pin "2") (pinfunction "2_2") (pintype "passive"))
      (node (ref "R22") (pin "1") (pinfunction "1_1") (pintype "passive"))
      (node (ref "R24") (pin "1") (pinfunction "1_1") (pintype "passive"))
      (node (ref "R25") (pin "2") (pinfunction "2_2") (pintype "passive"))
      (node (ref "R27") (pin "1") (pinfunction "1_1") (pintype "passive"))
      (node (ref "R29") (pin "1") (pinfunction "1_1") (pintype "passive"))
      (node (ref "R3") (pin "1") (pinfunction "1_1") (pintype "passive"))
      (node (ref "R30") (pin "2") (pinfunction "2_2") (pintype "passive"))
      (node (ref "R32") (pin "1") (pinfunction "1_1") (pintype "passive"))
      (node (ref "R34") (pin "1") (pinfunction "1_1") (pintype "passive"))
      (node (ref "R35") (pin "2") (pinfunction "2_2") (pintype "passive"))
      (node (ref "R37") (pin "1") (pinfunction "1_1") (pintype "passive"))
      (node (ref "R39") (pin "1") (pinfunction "1_1") (pintype "passive"))
      (node (ref "R40") (pin "2") (pinfunction "2_2") (pintype "passive"))
      (node (ref "R42") (pin "1") (pinfunction "1_1") (pintype "passive"))
      (node (ref "R44") (pin "1") (pinfunction "1_1") (pintype "passive"))
      (node (ref "R45") (pin "2") (pinfunction "2_2") (pintype "passive"))
      (node (ref "R47") (pin "1") (pinfunction "1_1") (pintype "passive"))
      (node (ref "R49") (pin "1") (pinfunction "1_1") (pintype "passive"))
      (node (ref "R50") (pin "2") (pinfunction "2_2") (pintype "passive"))
      (node (ref "R52") (pin "1") (pinfunction "1_1") (pintype "passive"))
      (node (ref "R54") (pin "1") (pinfunction "1_1") (pintype "passive"))
      (node (ref "R55") (pin "1") (pinfunction "1_1") (pintype "passive"))
      (node (ref "R56") (pin "1") (pinfunction "1_1") (pintype "passive"))
      (node (ref "R58") (pin "1") (pinfunction "1_1") (pintype "passive"))
      (node (ref "R59") (pin "1") (pinfunction "1_1") (pintype "passive"))
      (node (ref "R7") (pin "1") (pinfunction "1_1") (pintype "passive"))
      (node (ref "RANGE") (pin "3") (pinfunction "S_3") (pintype "passive"))
      (node (ref "RATE") (pin "P$3") (pinfunction "3_P$3") (pintype "passive"))
      (node (ref "RESET") (pin "GND") (pinfunction "SLEEVE_GND") (pintype "passive"))
      (node (ref "T1") (pin "2") (pinfunction "E_2") (pintype "passive"))
      (node (ref "T2") (pin "2") (pinfunction "E_2") (pintype "passive"))
    )
    (net (code "19") (name "Net-(CLK_IN-PadTIP)") (class "Default")
      (node (ref "CLK_IN") (pin "TIP") (pinfunction "TIP_TIP") (pintype "passive"))
      (node (ref "R6") (pin "2") (pinfunction "2_2") (pintype "passive"))
      (node (ref "R61") (pin "1") (pinfunction "1_1") (pintype "passive"))
    )
    (net (code "20") (name "Net-(CLK_IN-SWITCH)") (class "Default")
      (node (ref "CLK_IN") (pin "NORM") (pinfunction "SWITCH_NORM") (pintype "passive"))
      (node (ref "R11") (pin "1") (pinfunction "1_1") (pintype "passive"))
      (node (ref "R13") (pin "1") (pinfunction "1_1") (pintype "passive"))
    )
    (net (code "21") (name "Net-(CLOCK_OUT-PadTIP)") (class "Default")
      (node (ref "CLOCK_OUT") (pin "TIP") (pinfunction "TIP_TIP") (pintype "passive"))
      (node (ref "R14") (pin "1") (pinfunction "1_1") (pintype "passive"))
    )
    (net (code "22") (name "Net-(CV_OUT-PadTIP)") (class "Default")
      (node (ref "CV_OUT") (pin "TIP") (pinfunction "TIP_TIP") (pintype "passive"))
      (node (ref "R2") (pin "2") (pinfunction "2_2") (pintype "passive"))
      (node (ref "R4") (pin "2") (pinfunction "2_2") (pintype "passive"))
    )
    (net (code "23") (name "Net-(D1-PadA)") (class "Default")
      (node (ref "D1") (pin "A") (pinfunction "A_A") (pintype "passive"))
      (node (ref "JP2") (pin "10") (pinfunction "10_10") (pintype "passive"))
      (node (ref "JP2") (pin "9") (pinfunction "9_9") (pintype "passive"))
    )
    (net (code "24") (name "Net-(D2-PadC)") (class "Default")
      (node (ref "D2") (pin "C") (pinfunction "C_C") (pintype "passive"))
      (node (ref "JP2") (pin "1") (pinfunction "1_1") (pintype "passive"))
      (node (ref "JP2") (pin "2") (pinfunction "2_2") (pintype "passive"))
    )
    (net (code "25") (name "Net-(D3-PadA)") (class "Default")
      (node (ref "D3") (pin "A") (pinfunction "A_A") (pintype "passive"))
      (node (ref "R16") (pin "2") (pinfunction "2_2") (pintype "passive"))
      (node (ref "R18") (pin "2") (pinfunction "2_2") (pintype "passive"))
    )
    (net (code "26") (name "Net-(D3-PadC)") (class "Default")
      (node (ref "D3") (pin "C") (pinfunction "C_C") (pintype "passive"))
      (node (ref "GATE1") (pin "TIP") (pinfunction "TIP_TIP") (pintype "passive"))
    )
    (net (code "27") (name "Net-(D4-PadA)") (class "Default")
      (node (ref "D4") (pin "A") (pinfunction "A_A") (pintype "passive"))
      (node (ref "R21") (pin "2") (pinfunction "2_2") (pintype "passive"))
      (node (ref "R23") (pin "2") (pinfunction "2_2") (pintype "passive"))
    )
    (net (code "28") (name "Net-(D4-PadC)") (class "Default")
      (node (ref "D4") (pin "C") (pinfunction "C_C") (pintype "passive"))
      (node (ref "GATE2") (pin "TIP") (pinfunction "TIP_TIP") (pintype "passive"))
    )
    (net (code "29") (name "Net-(D5-PadA)") (class "Default")
      (node (ref "D5") (pin "A") (pinfunction "A_A") (pintype "passive"))
      (node (ref "R26") (pin "2") (pinfunction "2_2") (pintype "passive"))
      (node (ref "R28") (pin "2") (pinfunction "2_2") (pintype "passive"))
    )
    (net (code "30") (name "Net-(D5-PadC)") (class "Default")
      (node (ref "D5") (pin "C") (pinfunction "C_C") (pintype "passive"))
      (node (ref "GATE3") (pin "TIP") (pinfunction "TIP_TIP") (pintype "passive"))
    )
    (net (code "31") (name "Net-(D6-PadA)") (class "Default")
      (node (ref "D6") (pin "A") (pinfunction "A_A") (pintype "passive"))
      (node (ref "R31") (pin "2") (pinfunction "2_2") (pintype "passive"))
      (node (ref "R33") (pin "2") (pinfunction "2_2") (pintype "passive"))
    )
    (net (code "32") (name "Net-(D6-PadC)") (class "Default")
      (node (ref "D6") (pin "C") (pinfunction "C_C") (pintype "passive"))
      (node (ref "GATE4") (pin "TIP") (pinfunction "TIP_TIP") (pintype "passive"))
    )
    (net (code "33") (name "Net-(D7-PadA)") (class "Default")
      (node (ref "D7") (pin "A") (pinfunction "A_A") (pintype "passive"))
      (node (ref "R36") (pin "2") (pinfunction "2_2") (pintype "passive"))
      (node (ref "R38") (pin "2") (pinfunction "2_2") (pintype "passive"))
    )
    (net (code "34") (name "Net-(D7-PadC)") (class "Default")
      (node (ref "D7") (pin "C") (pinfunction "C_C") (pintype "passive"))
      (node (ref "GATE5") (pin "TIP") (pinfunction "TIP_TIP") (pintype "passive"))
    )
    (net (code "35") (name "Net-(D8-PadA)") (class "Default")
      (node (ref "D8") (pin "A") (pinfunction "A_A") (pintype "passive"))
      (node (ref "R41") (pin "2") (pinfunction "2_2") (pintype "passive"))
      (node (ref "R43") (pin "2") (pinfunction "2_2") (pintype "passive"))
    )
    (net (code "36") (name "Net-(D8-PadC)") (class "Default")
      (node (ref "D8") (pin "C") (pinfunction "C_C") (pintype "passive"))
      (node (ref "GATE6") (pin "TIP") (pinfunction "TIP_TIP") (pintype "passive"))
    )
    (net (code "37") (name "Net-(D9-PadA)") (class "Default")
      (node (ref "D9") (pin "A") (pinfunction "A_A") (pintype "passive"))
      (node (ref "R46") (pin "2") (pinfunction "2_2") (pintype "passive"))
      (node (ref "R48") (pin "2") (pinfunction "2_2") (pintype "passive"))
    )
    (net (code "38") (name "Net-(D9-PadC)") (class "Default")
      (node (ref "D9") (pin "C") (pinfunction "C_C") (pintype "passive"))
      (node (ref "GATE7") (pin "TIP") (pinfunction "TIP_TIP") (pintype "passive"))
    )
    (net (code "39") (name "Net-(D10-PadA)") (class "Default")
      (node (ref "D10") (pin "A") (pinfunction "A_A") (pintype "passive"))
      (node (ref "R51") (pin "2") (pinfunction "2_2") (pintype "passive"))
      (node (ref "R53") (pin "2") (pinfunction "2_2") (pintype "passive"))
    )
    (net (code "40") (name "Net-(D10-PadC)") (class "Default")
      (node (ref "D10") (pin "C") (pinfunction "C_C") (pintype "passive"))
      (node (ref "GATE8") (pin "TIP") (pinfunction "TIP_TIP") (pintype "passive"))
    )
    (net (code "41") (name "Net-(DIRSW-O)") (class "Default")
      (node (ref "DIRSW") (pin "1") (pinfunction "O_1") (pintype "passive"))
      (node (ref "IC5") (pin "10") (pinfunction "PD6(AIN0)_10") (pintype "bidirectional"))
      (node (ref "R58") (pin "2") (pinfunction "2_2") (pintype "passive"))
    )
    (net (code "42") (name "Net-(DIRSW-P)") (class "Default")
      (node (ref "DIRSW") (pin "2") (pinfunction "P_2") (pintype "passive"))
      (node (ref "R57") (pin "2") (pinfunction "2_2") (pintype "passive"))
    )
    (net (code "43") (name "Net-(DIRSW-S)") (class "Default")
      (node (ref "DIRSW") (pin "3") (pinfunction "S_3") (pintype "passive"))
      (node (ref "IC5") (pin "11") (pinfunction "PD7(AIN1)_11") (pintype "bidirectional"))
      (node (ref "R59") (pin "2") (pinfunction "2_2") (pintype "passive"))
    )
    (net (code "44") (name "Net-(FADER1B-C)") (class "Default")
      (node (ref "FADER1") (pin "K") (pinfunction "C_K") (pintype "passive"))
      (node (ref "R15") (pin "1") (pinfunction "1_1") (pintype "passive"))
    )
    (net (code "45") (name "Net-(FADER2B-C)") (class "Default")
      (node (ref "FADER2") (pin "K") (pinfunction "C_K") (pintype "passive"))
      (node (ref "R20") (pin "1") (pinfunction "1_1") (pintype "passive"))
    )
    (net (code "46") (name "Net-(FADER3B-C)") (class "Default")
      (node (ref "FADER3") (pin "K") (pinfunction "C_K") (pintype "passive"))
      (node (ref "R25") (pin "1") (pinfunction "1_1") (pintype "passive"))
    )
    (net (code "47") (name "Net-(FADER4B-C)") (class "Default")
      (node (ref "FADER4") (pin "K") (pinfunction "C_K") (pintype "passive"))
      (node (ref "R30") (pin "1") (pinfunction "1_1") (pintype "passive"))
    )
    (net (code "48") (name "Net-(FADER5B-C)") (class "Default")
      (node (ref "FADER5") (pin "K") (pinfunction "C_K") (pintype "passive"))
      (node (ref "R35") (pin "1") (pinfunction "1_1") (pintype "passive"))
    )
    (net (code "49") (name "Net-(FADER6B-C)") (class "Default")
      (node (ref "FADER6") (pin "K") (pinfunction "C_K") (pintype "passive"))
      (node (ref "R40") (pin "1") (pinfunction "1_1") (pintype "passive"))
    )
    (net (code "50") (name "Net-(FADER7B-C)") (class "Default")
      (node (ref "FADER7") (pin "K") (pinfunction "C_K") (pintype "passive"))
      (node (ref "R45") (pin "1") (pinfunction "1_1") (pintype "passive"))
    )
    (net (code "51") (name "Net-(FADER8B-C)") (class "Default")
      (node (ref "FADER8") (pin "K") (pinfunction "C_K") (pintype "passive"))
      (node (ref "R50") (pin "1") (pinfunction "1_1") (pintype "passive"))
    )
    (net (code "52") (name "Net-(GLIDE-1)") (class "Default")
      (node (ref "GLIDE") (pin "P$1") (pinfunction "1_P$1") (pintype "passive"))
      (node (ref "R1") (pin "2") (pinfunction "2_2") (pintype "passive"))
    )
    (net (code "53") (name "Net-(GLIDE-2)") (class "Default")
      (node (ref "C3") (pin "1") (pinfunction "1_1") (pintype "passive"))
      (node (ref "GLIDE") (pin "P$2") (pinfunction "2_P$2") (pintype "passive"))
      (node (ref "GLIDE") (pin "P$3") (pinfunction "3_P$3") (pintype "passive"))
      (node (ref "IC2") (pin "3") (pinfunction "+IN_3") (pintype "input"))
    )
    (net (code "54") (name "Net-(IC2A--IN)") (class "Default")
      (node (ref "C6") (pin "1") (pinfunction "1_1") (pintype "passive"))
      (node (ref "IC2") (pin "2") (pinfunction "-IN_2") (pintype "input"))
      (node (ref "R2") (pin "1") (pinfunction "1_1") (pintype "passive"))
      (node (ref "R3") (pin "2") (pinfunction "2_2") (pintype "passive"))
    )
    (net (code "55") (name "Net-(IC2A-OUT)") (class "Default")
      (node (ref "C6") (pin "2") (pinfunction "2_2") (pintype "passive"))
      (node (ref "IC2") (pin "1") (pinfunction "OUT_1") (pintype "output"))
      (node (ref "R4") (pin "1") (pinfunction "1_1") (pintype "passive"))
    )
    (net (code "56") (name "Net-(IC2B-+IN)") (class "Default")
      (node (ref "IC2") (pin "5") (pinfunction "+IN_5") (pintype "input"))
      (node (ref "R61") (pin "2") (pinfunction "2_2") (pintype "passive"))
    )
    (net (code "57") (name "Net-(IC2B--IN)") (class "Default")
      (node (ref "IC2") (pin "6") (pinfunction "-IN_6") (pintype "input"))
      (node (ref "IC2") (pin "7") (pinfunction "OUT_7") (pintype "output"))
      (node (ref "R14") (pin "2") (pinfunction "2_2") (pintype "passive"))
    )
    (net (code "58") (name "Net-(IC2C--IN)") (class "Default")
      (node (ref "C7") (pin "1") (pinfunction "1_1") (pintype "passive"))
      (node (ref "IC2") (pin "9") (pinfunction "-IN_9") (pintype "input"))
      (node (ref "R11") (pin "2") (pinfunction "2_2") (pintype "passive"))
      (node (ref "R12") (pin "1") (pinfunction "1_1") (pintype "passive"))
    )
    (net (code "59") (name "Net-(IC2C-OUT)") (class "Default")
      (node (ref "C7") (pin "2") (pinfunction "2_2") (pintype "passive"))
      (node (ref "IC2") (pin "8") (pinfunction "OUT_8") (pintype "output"))
      (node (ref "R13") (pin "2") (pinfunction "2_2") (pintype "passive"))
    )
    (net (code "60") (name "Net-(IC2D-+IN)") (class "Default")
      (node (ref "IC2") (pin "12") (pinfunction "+IN_12") (pintype "input"))
      (node (ref "R60") (pin "1") (pinfunction "1_1") (pintype "passive"))
      (node (ref "R62") (pin "2") (pinfunction "2_2") (pintype "passive"))
    )
    (net (code "61") (name "Net-(IC2D--IN)") (class "Default")
      (node (ref "IC2") (pin "13") (pinfunction "-IN_13") (pintype "input"))
      (node (ref "IC2") (pin "14") (pinfunction "OUT_14") (pintype "output"))
      (node (ref "R1") (pin "1") (pinfunction "1_1") (pintype "passive"))
    )
    (net (code "62") (name "Net-(IC3A--IN)") (class "Default")
      (node (ref "C10") (pin "1") (pinfunction "1_1") (pintype "passive"))
      (node (ref "IC3") (pin "2") (pinfunction "-IN_2") (pintype "input"))
      (node (ref "R16") (pin "1") (pinfunction "1_1") (pintype "passive"))
      (node (ref "R17") (pin "2") (pinfunction "2_2") (pintype "passive"))
    )
    (net (code "63") (name "Net-(IC3A-OUT)") (class "Default")
      (node (ref "C10") (pin "2") (pinfunction "2_2") (pintype "passive"))
      (node (ref "IC3") (pin "1") (pinfunction "OUT_1") (pintype "output"))
      (node (ref "R18") (pin "1") (pinfunction "1_1") (pintype "passive"))
    )
    (net (code "64") (name "Net-(IC3B--IN)") (class "Default")
      (node (ref "C12") (pin "1") (pinfunction "1_1") (pintype "passive"))
      (node (ref "IC3") (pin "6") (pinfunction "-IN_6") (pintype "input"))
      (node (ref "R21") (pin "1") (pinfunction "1_1") (pintype "passive"))
      (node (ref "R22") (pin "2") (pinfunction "2_2") (pintype "passive"))
    )
    (net (code "65") (name "Net-(IC3B-OUT)") (class "Default")
      (node (ref "C12") (pin "2") (pinfunction "2_2") (pintype "passive"))
      (node (ref "IC3") (pin "7") (pinfunction "OUT_7") (pintype "output"))
      (node (ref "R23") (pin "1") (pinfunction "1_1") (pintype "passive"))
    )
    (net (code "66") (name "Net-(IC3C--IN)") (class "Default")
      (node (ref "C14") (pin "1") (pinfunction "1_1") (pintype "passive"))
      (node (ref "IC3") (pin "9") (pinfunction "-IN_9") (pintype "input"))
      (node (ref "R26") (pin "1") (pinfunction "1_1") (pintype "passive"))
      (node (ref "R27") (pin "2") (pinfunction "2_2") (pintype "passive"))
    )
    (net (code "67") (name "Net-(IC3C-OUT)") (class "Default")
      (node (ref "C14") (pin "2") (pinfunction "2_2") (pintype "passive"))
      (node (ref "IC3") (pin "8") (pinfunction "OUT_8") (pintype "output"))
      (node (ref "R28") (pin "1") (pinfunction "1_1") (pintype "passive"))
    )
    (net (code "68") (name "Net-(IC3D--IN)") (class "Default")
      (node (ref "C16") (pin "1") (pinfunction "1_1") (pintype "passive"))
      (node (ref "IC3") (pin "13") (pinfunction "-IN_13") (pintype "input"))
      (node (ref "R31") (pin "1") (pinfunction "1_1") (pintype "passive"))
      (node (ref "R32") (pin "2") (pinfunction "2_2") (pintype "passive"))
    )
    (net (code "69") (name "Net-(IC3D-OUT)") (class "Default")
      (node (ref "C16") (pin "2") (pinfunction "2_2") (pintype "passive"))
      (node (ref "IC3") (pin "14") (pinfunction "OUT_14") (pintype "output"))
      (node (ref "R33") (pin "1") (pinfunction "1_1") (pintype "passive"))
    )
    (net (code "70") (name "Net-(IC4A--IN)") (class "Default")
      (node (ref "C18") (pin "1") (pinfunction "1_1") (pintype "passive"))
      (node (ref "IC4") (pin "2") (pinfunction "-IN_2") (pintype "input"))
      (node (ref "R36") (pin "1") (pinfunction "1_1") (pintype "passive"))
      (node (ref "R37") (pin "2") (pinfunction "2_2") (pintype "passive"))
    )
    (net (code "71") (name "Net-(IC4A-OUT)") (class "Default")
      (node (ref "C18") (pin "2") (pinfunction "2_2") (pintype "passive"))
      (node (ref "IC4") (pin "1") (pinfunction "OUT_1") (pintype "output"))
      (node (ref "R38") (pin "1") (pinfunction "1_1") (pintype "passive"))
    )
    (net (code "72") (name "Net-(IC4B--IN)") (class "Default")
      (node (ref "C20") (pin "1") (pinfunction "1_1") (pintype "passive"))
      (node (ref "IC4") (pin "6") (pinfunction "-IN_6") (pintype "input"))
      (node (ref "R41") (pin "1") (pinfunction "1_1") (pintype "passive"))
      (node (ref "R42") (pin "2") (pinfunction "2_2") (pintype "passive"))
    )
    (net (code "73") (name "Net-(IC4B-OUT)") (class "Default")
      (node (ref "C20") (pin "2") (pinfunction "2_2") (pintype "passive"))
      (node (ref "IC4") (pin "7") (pinfunction "OUT_7") (pintype "output"))
      (node (ref "R43") (pin "1") (pinfunction "1_1") (pintype "passive"))
    )
    (net (code "74") (name "Net-(IC4C--IN)") (class "Default")
      (node (ref "C22") (pin "1") (pinfunction "1_1") (pintype "passive"))
      (node (ref "IC4") (pin "9") (pinfunction "-IN_9") (pintype "input"))
      (node (ref "R46") (pin "1") (pinfunction "1_1") (pintype "passive"))
      (node (ref "R47") (pin "2") (pinfunction "2_2") (pintype "passive"))
    )
    (net (code "75") (name "Net-(IC4C-OUT)") (class "Default")
      (node (ref "C22") (pin "2") (pinfunction "2_2") (pintype "passive"))
      (node (ref "IC4") (pin "8") (pinfunction "OUT_8") (pintype "output"))
      (node (ref "R48") (pin "1") (pinfunction "1_1") (pintype "passive"))
    )
    (net (code "76") (name "Net-(IC4D--IN)") (class "Default")
      (node (ref "C24") (pin "1") (pinfunction "1_1") (pintype "passive"))
      (node (ref "IC4") (pin "13") (pinfunction "-IN_13") (pintype "input"))
      (node (ref "R51") (pin "1") (pinfunction "1_1") (pintype "passive"))
      (node (ref "R52") (pin "2") (pinfunction "2_2") (pintype "passive"))
    )
    (net (code "77") (name "Net-(IC4D-OUT)") (class "Default")
      (node (ref "C24") (pin "2") (pinfunction "2_2") (pintype "passive"))
      (node (ref "IC4") (pin "14") (pinfunction "OUT_14") (pintype "output"))
      (node (ref "R53") (pin "1") (pinfunction "1_1") (pintype "passive"))
    )
    (net (code "78") (name "Net-(IC5-ADC7)") (class "Default")
      (node (ref "IC5") (pin "22") (pinfunction "ADC7_22") (pintype "bidirectional"))
      (node (ref "RATE") (pin "P$2") (pinfunction "2_P$2") (pintype "passive"))
    )
    (net (code "79") (name "Net-(IC5-PB6(XTAL1{slash}TOSC1))") (class "Default")
      (node (ref "C1") (pin "1") (pinfunction "1_1") (pintype "passive"))
      (node (ref "IC5") (pin "7") (pinfunction "PB6(XTAL1/TOSC1)_7") (pintype "bidirectional"))
      (node (ref "Q1") (pin "2") (pinfunction "2_2") (pintype "passive"))
    )
    (net (code "80") (name "Net-(IC5-PB7(XTAL2{slash}TOSC2))") (class "Default")
      (node (ref "C2") (pin "1") (pinfunction "1_1") (pintype "passive"))
      (node (ref "IC5") (pin "8") (pinfunction "PB7(XTAL2/TOSC2)_8") (pintype "bidirectional"))
      (node (ref "Q1") (pin "1") (pinfunction "1_1") (pintype "passive"))
    )
    (net (code "81") (name "Net-(IC5-PD4(XCK{slash}T0))") (class "Default")
      (node (ref "IC5") (pin "2") (pinfunction "PD4(XCK/T0)_2") (pintype "bidirectional"))
      (node (ref "R55") (pin "2") (pinfunction "2_2") (pintype "passive"))
      (node (ref "SW1") (pin "1") (pinfunction "3_1") (pintype "bidirectional"))
      (node (ref "SW1") (pin "2") (pinfunction "1_2") (pintype "bidirectional"))
    )
    (net (code "82") (name "Net-(IC5-PD5(T1))") (class "Default")
      (node (ref "IC5") (pin "9") (pinfunction "PD5(T1)_9") (pintype "bidirectional"))
      (node (ref "SW1") (pin "A") (pinfunction "A_A") (pintype "passive"))
    )
    (net (code "83") (name "Net-(IC6-Y0)") (class "Default")
      (node (ref "FADER1") (pin "2") (pinfunction "2_2") (pintype "passive"))
      (node (ref "IC6") (pin "13") (pinfunction "Y0_13") (pintype "bidirectional"))
    )
    (net (code "84") (name "Net-(IC6-Y1)") (class "Default")
      (node (ref "FADER2") (pin "2") (pinfunction "2_2") (pintype "passive"))
      (node (ref "IC6") (pin "14") (pinfunction "Y1_14") (pintype "bidirectional"))
    )
    (net (code "85") (name "Net-(IC6-Y2)") (class "Default")
      (node (ref "FADER3") (pin "2") (pinfunction "2_2") (pintype "passive"))
      (node (ref "IC6") (pin "15") (pinfunction "Y2_15") (pintype "bidirectional"))
    )
    (net (code "86") (name "Net-(IC6-Y3)") (class "Default")
      (node (ref "FADER4") (pin "2") (pinfunction "2_2") (pintype "passive"))
      (node (ref "IC6") (pin "12") (pinfunction "Y3_12") (pintype "bidirectional"))
    )
    (net (code "87") (name "Net-(IC6-Y4)") (class "Default")
      (node (ref "FADER5") (pin "2") (pinfunction "2_2") (pintype "passive"))
      (node (ref "IC6") (pin "1") (pinfunction "Y4_1") (pintype "bidirectional"))
    )
    (net (code "88") (name "Net-(IC6-Y5)") (class "Default")
      (node (ref "FADER6") (pin "2") (pinfunction "2_2") (pintype "passive"))
      (node (ref "IC6") (pin "5") (pinfunction "Y5_5") (pintype "bidirectional"))
    )
    (net (code "89") (name "Net-(IC6-Y6)") (class "Default")
      (node (ref "FADER7") (pin "2") (pinfunction "2_2") (pintype "passive"))
      (node (ref "IC6") (pin "2") (pinfunction "Y6_2") (pintype "bidirectional"))
    )
    (net (code "90") (name "Net-(IC6-Y7)") (class "Default")
      (node (ref "FADER8") (pin "2") (pinfunction "2_2") (pintype "passive"))
      (node (ref "IC6") (pin "4") (pinfunction "Y7_4") (pintype "bidirectional"))
    )
    (net (code "91") (name "Net-(IC6-Z)") (class "Default")
      (node (ref "IC6") (pin "3") (pinfunction "Z_3") (pintype "bidirectional"))
      (node (ref "R60") (pin "2") (pinfunction "2_2") (pintype "passive"))
    )
    (net (code "92") (name "Net-(JP2-Pad13)") (class "Default")
      (node (ref "JP2") (pin "13") (pinfunction "13_13") (pintype "passive"))
      (node (ref "JP2") (pin "14") (pinfunction "14_14") (pintype "passive"))
    )
    (net (code "93") (name "Net-(JP2-Pad15)") (class "Default")
      (node (ref "JP2") (pin "15") (pinfunction "15_15") (pintype "passive"))
      (node (ref "JP2") (pin "16") (pinfunction "16_16") (pintype "passive"))
    )
    (net (code "94") (name "Net-(R9-Pad2)") (class "Default")
      (node (ref "R9") (pin "2") (pinfunction "2_2") (pintype "passive"))
      (node (ref "RESET") (pin "TIP") (pinfunction "TIP_TIP") (pintype "passive"))
    )
    (net (code "95") (name "Net-(RANGE-P)") (class "Default")
      (node (ref "R62") (pin "1") (pinfunction "1_1") (pintype "passive"))
      (node (ref "RANGE") (pin "2") (pinfunction "P_2") (pintype "passive"))
    )
    (net (code "96") (name "Net-(SW1B-C)") (class "Default")
      (node (ref "R56") (pin "2") (pinfunction "2_2") (pintype "passive"))
      (node (ref "SW1") (pin "K") (pinfunction "C_K") (pintype "passive"))
    )
    (net (code "97") (name "Net-(T1-B)") (class "Default")
      (node (ref "R6") (pin "1") (pinfunction "1_1") (pintype "passive"))
      (node (ref "R7") (pin "2") (pinfunction "2_2") (pintype "passive"))
      (node (ref "T1") (pin "1") (pinfunction "B_1") (pintype "passive"))
    )
    (net (code "98") (name "Net-(T2-B)") (class "Default")
      (node (ref "R10") (pin "2") (pinfunction "2_2") (pintype "passive"))
      (node (ref "R9") (pin "1") (pinfunction "1_1") (pintype "passive"))
      (node (ref "T2") (pin "1") (pinfunction "B_1") (pintype "passive"))
    )
    (net (code "99") (name "RESET") (class "Default")
      (node (ref "IC5") (pin "1") (pinfunction "PD3(INT1)_1") (pintype "bidirectional"))
      (node (ref "R8") (pin "1") (pinfunction "1_1") (pintype "passive"))
      (node (ref "T2") (pin "3") (pinfunction "C_3") (pintype "passive"))
    )
    (net (code "100") (name "RST") (class "Default")
      (node (ref "IC5") (pin "29") (pinfunction "PC6(/RESET)_29") (pintype "bidirectional"))
      (node (ref "ISP1") (pin "5") (pinfunction "RST_5") (pintype "output"))
    )
    (net (code "101") (name "unconnected-(CLOCK_OUT-SWITCH-PadNORM)") (class "Default")
      (node (ref "CLOCK_OUT") (pin "NORM") (pinfunction "SWITCH_NORM") (pintype "passive"))
    )
    (net (code "102") (name "unconnected-(CV_OUT-SWITCH-PadNORM)") (class "Default")
      (node (ref "CV_OUT") (pin "NORM") (pinfunction "SWITCH_NORM") (pintype "passive"))
    )
    (net (code "103") (name "unconnected-(GATE1-SWITCH-PadNORM)") (class "Default")
      (node (ref "GATE1") (pin "NORM") (pinfunction "SWITCH_NORM") (pintype "passive"))
    )
    (net (code "104") (name "unconnected-(GATE2-SWITCH-PadNORM)") (class "Default")
      (node (ref "GATE2") (pin "NORM") (pinfunction "SWITCH_NORM") (pintype "passive"))
    )
    (net (code "105") (name "unconnected-(GATE3-SWITCH-PadNORM)") (class "Default")
      (node (ref "GATE3") (pin "NORM") (pinfunction "SWITCH_NORM") (pintype "passive"))
    )
    (net (code "106") (name "unconnected-(GATE4-SWITCH-PadNORM)") (class "Default")
      (node (ref "GATE4") (pin "NORM") (pinfunction "SWITCH_NORM") (pintype "passive"))
    )
    (net (code "107") (name "unconnected-(GATE5-SWITCH-PadNORM)") (class "Default")
      (node (ref "GATE5") (pin "NORM") (pinfunction "SWITCH_NORM") (pintype "passive"))
    )
    (net (code "108") (name "unconnected-(GATE6-SWITCH-PadNORM)") (class "Default")
      (node (ref "GATE6") (pin "NORM") (pinfunction "SWITCH_NORM") (pintype "passive"))
    )
    (net (code "109") (name "unconnected-(GATE7-SWITCH-PadNORM)") (class "Default")
      (node (ref "GATE7") (pin "NORM") (pinfunction "SWITCH_NORM") (pintype "passive"))
    )
    (net (code "110") (name "unconnected-(GATE8-SWITCH-PadNORM)") (class "Default")
      (node (ref "GATE8") (pin "NORM") (pinfunction "SWITCH_NORM") (pintype "passive"))
    )
    (net (code "111") (name "unconnected-(IC5-AREF-Pad20)") (class "Default")
      (node (ref "IC5") (pin "20") (pinfunction "AREF_20") (pintype "bidirectional"))
    )
    (net (code "112") (name "unconnected-(IC5-PD0(RXD)-Pad30)") (class "Default")
      (node (ref "IC5") (pin "30") (pinfunction "PD0(RXD)_30") (pintype "bidirectional"))
    )
    (net (code "113") (name "unconnected-(IC5-PD1(TXD)-Pad31)") (class "Default")
      (node (ref "IC5") (pin "31") (pinfunction "PD1(TXD)_31") (pintype "bidirectional"))
    )
    (net (code "114") (name "unconnected-(RANGE-O-Pad1)") (class "Default")
      (node (ref "RANGE") (pin "1") (pinfunction "O_1") (pintype "passive"))
    )
    (net (code "115") (name "unconnected-(RESET-SWITCH-PadNORM)") (class "Default")
      (node (ref "RESET") (pin "NORM") (pinfunction "SWITCH_NORM") (pintype "passive"))
    )
  )
)
